# IPSv3_0.net
KiCad netlist of a schematic drawn in EAGLE
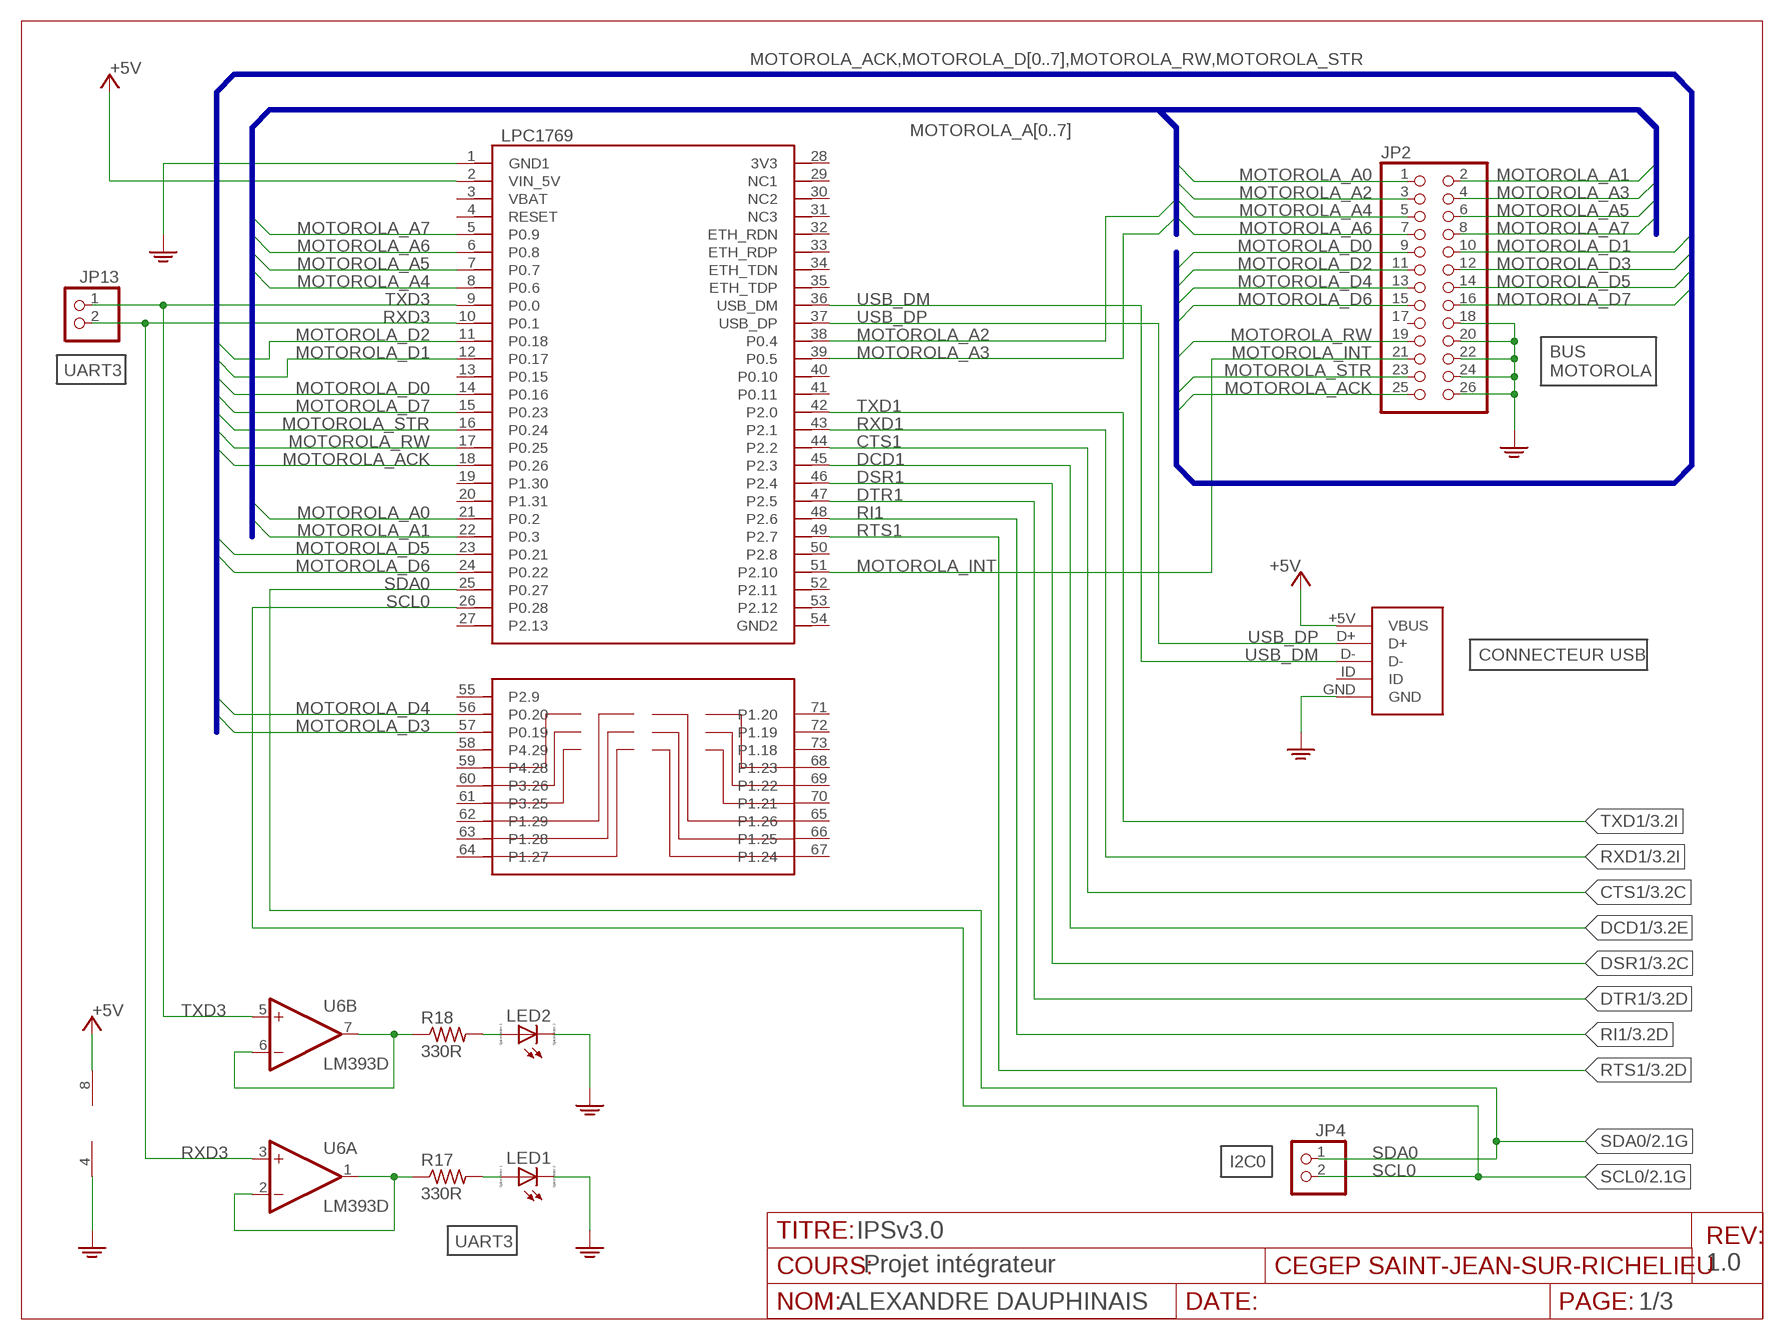
[diagram p0: schematic, sheet 1]
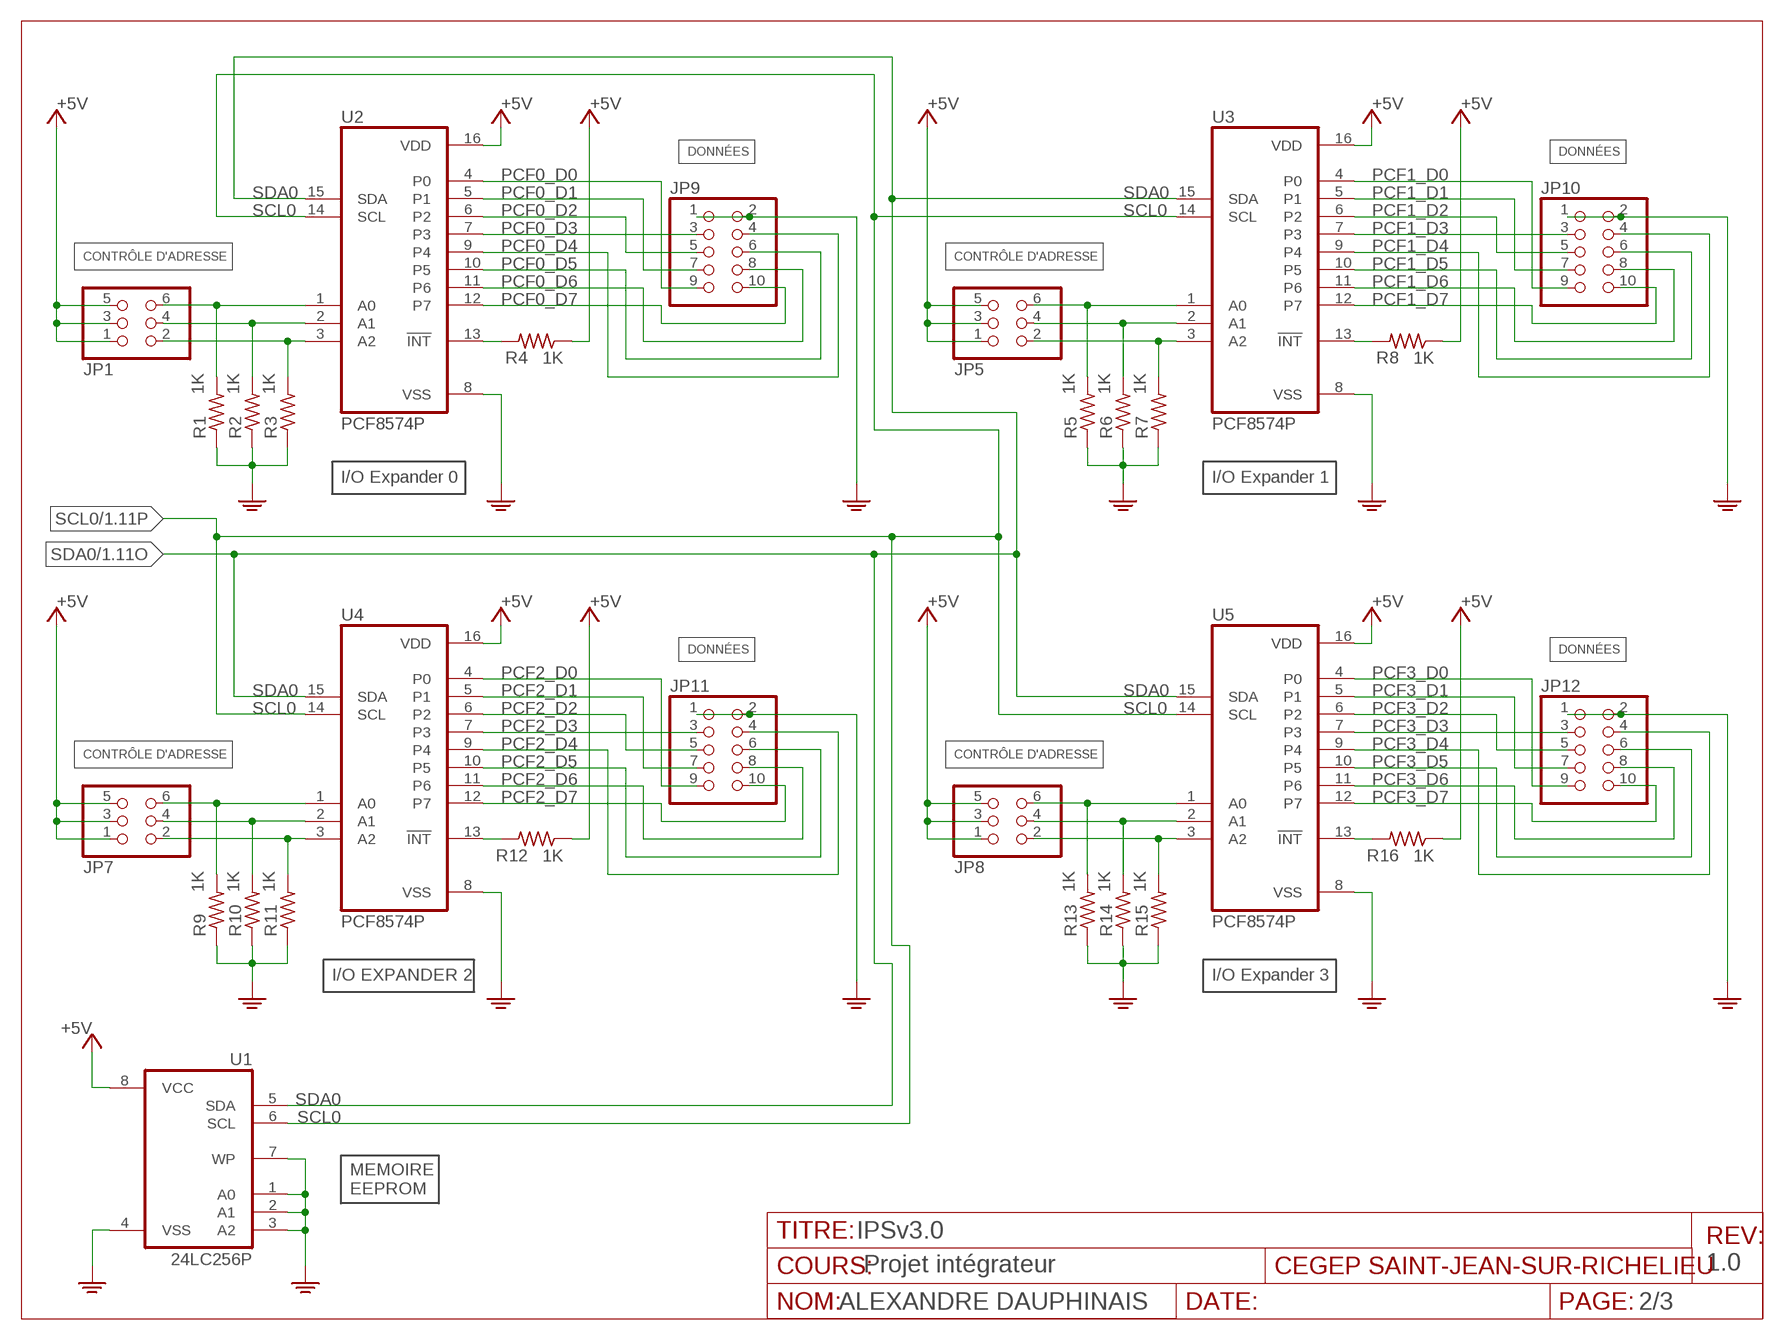
[diagram p1: schematic, sheet 2]
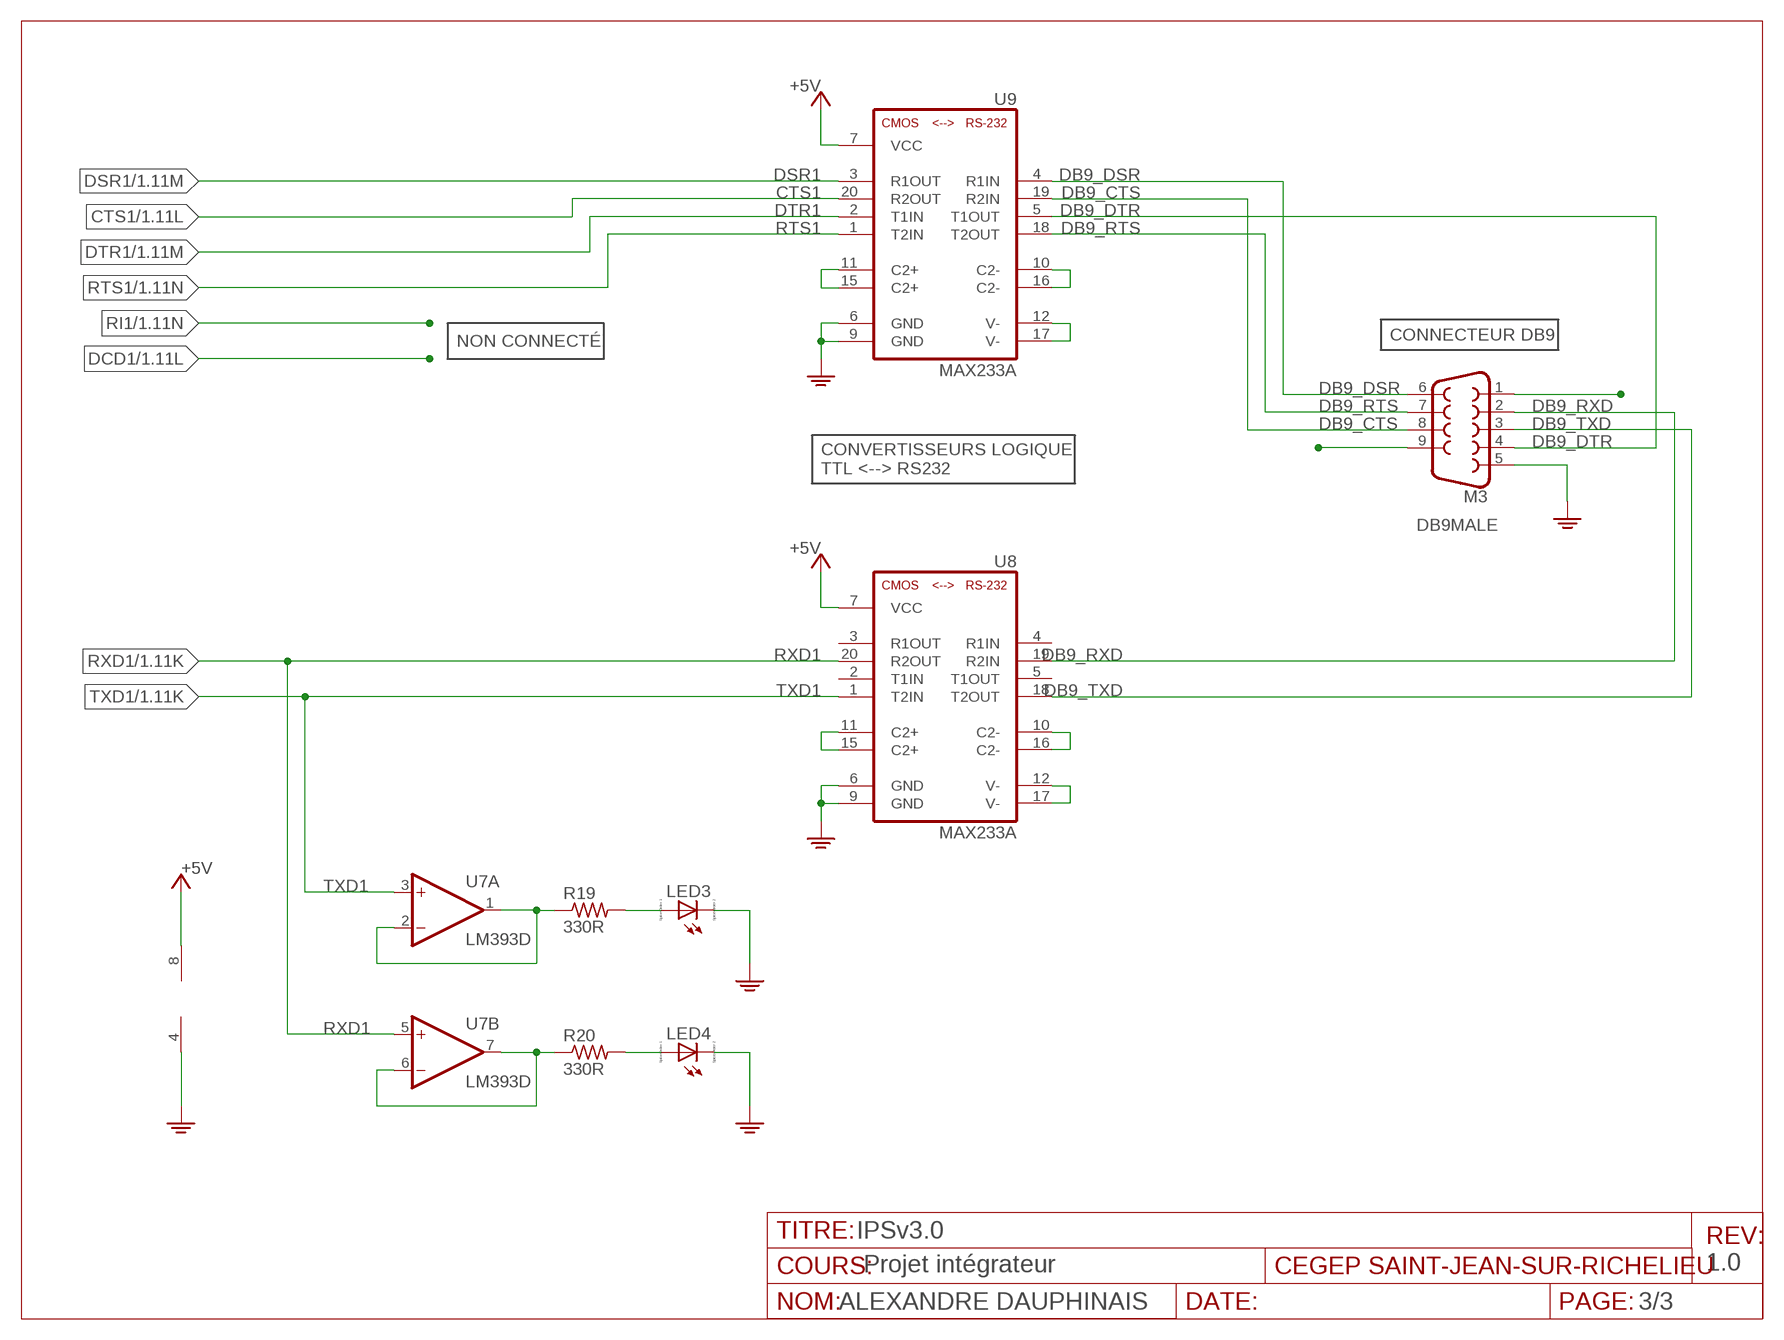
[diagram p2: schematic, sheet 3]

(export (version "E")
  (design (tool "Eeschema 10.0.6"))
  (components
    (comp (ref "JP2")
      (value "PINHD-02X13M")
      (footprint "eagle-import:02X13M")
      (libsource (lib "eagle-import") (part "PINHD-02X13M"))
    )
    (comp (ref "JP4")
      (value "PINHD-01X02M")
      (footprint "eagle-import:01X02M")
      (libsource (lib "eagle-import") (part "PINHD-01X02M"))
    )
    (comp (ref "JP13")
      (value "PINHD-01X02M")
      (footprint "eagle-import:01X02M")
      (libsource (lib "eagle-import") (part "PINHD-01X02M"))
    )
    (comp (ref "LED1")
      (value "LED_BLEU")
      (footprint "eagle-import:LED_1206")
      (libsource (lib "eagle-import") (part "LED_E"))
    )
    (comp (ref "LED2")
      (value "LED_JAUNE")
      (footprint "eagle-import:LED_1206")
      (libsource (lib "eagle-import") (part "LED_E"))
    )
    (comp (ref "M1")
      (value "LPC_LPC1769")
      (footprint "eagle-import:LPC_LPC1769")
      (libsource (lib "eagle-import") (part "LPC_LPC1769"))
    )
    (comp (ref "M2")
      (value "USB-MICRO-BREAKOUT")
      (footprint "eagle-import:USB-MICRO-BREAKOUT")
      (libsource (lib "eagle-import") (part "USB-MICRO-BREAKOUT"))
    )
    (comp (ref "R17")
      (value "330R")
      (footprint "eagle-import:R1206")
      (libsource (lib "eagle-import") (part "R-US_R1206"))
    )
    (comp (ref "R18")
      (value "330R")
      (footprint "eagle-import:R1206")
      (libsource (lib "eagle-import") (part "R-US_R1206"))
    )
    (comp (ref "U6")
      (value "LM393D")
      (footprint "eagle-import:SO08")
      (libsource (lib "eagle-import") (part "LM393D"))
    )
    (comp (ref "JP1")
      (value "PINHD-02X03M")
      (footprint "eagle-import:02X03M")
      (libsource (lib "eagle-import") (part "PINHD-02X03M"))
    )
    (comp (ref "JP5")
      (value "PINHD-02X03M")
      (footprint "eagle-import:02X03M")
      (libsource (lib "eagle-import") (part "PINHD-02X03M"))
    )
    (comp (ref "JP7")
      (value "PINHD-02X03M")
      (footprint "eagle-import:02X03M")
      (libsource (lib "eagle-import") (part "PINHD-02X03M"))
    )
    (comp (ref "JP8")
      (value "PINHD-02X03M")
      (footprint "eagle-import:02X03M")
      (libsource (lib "eagle-import") (part "PINHD-02X03M"))
    )
    (comp (ref "JP9")
      (value "PINHD-02X05M")
      (footprint "eagle-import:02X05M")
      (libsource (lib "eagle-import") (part "PINHD-02X05M"))
    )
    (comp (ref "JP10")
      (value "PINHD-02X05M")
      (footprint "eagle-import:02X05M")
      (libsource (lib "eagle-import") (part "PINHD-02X05M"))
    )
    (comp (ref "JP11")
      (value "PINHD-02X05M")
      (footprint "eagle-import:02X05M")
      (libsource (lib "eagle-import") (part "PINHD-02X05M"))
    )
    (comp (ref "JP12")
      (value "PINHD-02X05M")
      (footprint "eagle-import:02X05M")
      (libsource (lib "eagle-import") (part "PINHD-02X05M"))
    )
    (comp (ref "R1")
      (value "1K")
      (footprint "eagle-import:R1206")
      (libsource (lib "eagle-import") (part "R-US_R1206"))
    )
    (comp (ref "R2")
      (value "1K")
      (footprint "eagle-import:R1206")
      (libsource (lib "eagle-import") (part "R-US_R1206"))
    )
    (comp (ref "R3")
      (value "1K")
      (footprint "eagle-import:R1206")
      (libsource (lib "eagle-import") (part "R-US_R1206"))
    )
    (comp (ref "R4")
      (value "1K")
      (footprint "eagle-import:R1206")
      (libsource (lib "eagle-import") (part "R-US_R1206"))
    )
    (comp (ref "R5")
      (value "1K")
      (footprint "eagle-import:R1206")
      (libsource (lib "eagle-import") (part "R-US_R1206"))
    )
    (comp (ref "R6")
      (value "1K")
      (footprint "eagle-import:R1206")
      (libsource (lib "eagle-import") (part "R-US_R1206"))
    )
    (comp (ref "R7")
      (value "1K")
      (footprint "eagle-import:R1206")
      (libsource (lib "eagle-import") (part "R-US_R1206"))
    )
    (comp (ref "R8")
      (value "1K")
      (footprint "eagle-import:R1206")
      (libsource (lib "eagle-import") (part "R-US_R1206"))
    )
    (comp (ref "R9")
      (value "1K")
      (footprint "eagle-import:R1206")
      (libsource (lib "eagle-import") (part "R-US_R1206"))
    )
    (comp (ref "R10")
      (value "1K")
      (footprint "eagle-import:R1206")
      (libsource (lib "eagle-import") (part "R-US_R1206"))
    )
    (comp (ref "R11")
      (value "1K")
      (footprint "eagle-import:R1206")
      (libsource (lib "eagle-import") (part "R-US_R1206"))
    )
    (comp (ref "R12")
      (value "1K")
      (footprint "eagle-import:R1206")
      (libsource (lib "eagle-import") (part "R-US_R1206"))
    )
    (comp (ref "R13")
      (value "1K")
      (footprint "eagle-import:R1206")
      (libsource (lib "eagle-import") (part "R-US_R1206"))
    )
    (comp (ref "R14")
      (value "1K")
      (footprint "eagle-import:R1206")
      (libsource (lib "eagle-import") (part "R-US_R1206"))
    )
    (comp (ref "R15")
      (value "1K")
      (footprint "eagle-import:R1206")
      (libsource (lib "eagle-import") (part "R-US_R1206"))
    )
    (comp (ref "R16")
      (value "1K")
      (footprint "eagle-import:R1206")
      (libsource (lib "eagle-import") (part "R-US_R1206"))
    )
    (comp (ref "U1")
      (value "24LC256P")
      (footprint "eagle-import:DIL08")
      (libsource (lib "eagle-import") (part "24LC256P"))
    )
    (comp (ref "U2")
      (value "PCF8574P")
      (footprint "eagle-import:DIL16")
      (libsource (lib "eagle-import") (part "PCF8574P"))
    )
    (comp (ref "U3")
      (value "PCF8574P")
      (footprint "eagle-import:DIL16")
      (libsource (lib "eagle-import") (part "PCF8574P"))
    )
    (comp (ref "U4")
      (value "PCF8574P")
      (footprint "eagle-import:DIL16")
      (libsource (lib "eagle-import") (part "PCF8574P"))
    )
    (comp (ref "U5")
      (value "PCF8574P")
      (footprint "eagle-import:DIL16")
      (libsource (lib "eagle-import") (part "PCF8574P"))
    )
    (comp (ref "LED3")
      (value "LED_JAUNE")
      (footprint "eagle-import:LED_1206")
      (libsource (lib "eagle-import") (part "LED_E"))
    )
    (comp (ref "LED4")
      (value "LED_BLEU")
      (footprint "eagle-import:LED_1206")
      (libsource (lib "eagle-import") (part "LED_E"))
    )
    (comp (ref "M3")
      (value "DB9MALE")
      (footprint "eagle-import:DB9")
      (libsource (lib "eagle-import") (part "DB9FEMALE"))
    )
    (comp (ref "R19")
      (value "330R")
      (footprint "eagle-import:R1206")
      (libsource (lib "eagle-import") (part "R-US_R1206"))
    )
    (comp (ref "R20")
      (value "330R")
      (footprint "eagle-import:R1206")
      (libsource (lib "eagle-import") (part "R-US_R1206"))
    )
    (comp (ref "U7")
      (value "LM393D")
      (footprint "eagle-import:SO08")
      (libsource (lib "eagle-import") (part "LM393D"))
    )
    (comp (ref "U8")
      (value "MAX233A")
      (footprint "eagle-import:DIL20")
      (libsource (lib "eagle-import") (part "MAX233ACPP"))
    )
    (comp (ref "U9")
      (value "MAX233A")
      (footprint "eagle-import:DIL20")
      (libsource (lib "eagle-import") (part "MAX233ACPP"))
    )
  )
  (nets
    (net (code "1") (name "+5V") (class "Default")
      (node (ref "JP1") (pin "1") (pinfunction "1_1") (pintype "passive"))
      (node (ref "JP1") (pin "3") (pinfunction "3_3") (pintype "passive"))
      (node (ref "JP1") (pin "5") (pinfunction "5_5") (pintype "passive"))
      (node (ref "JP5") (pin "1") (pinfunction "1_1") (pintype "passive"))
      (node (ref "JP5") (pin "3") (pinfunction "3_3") (pintype "passive"))
      (node (ref "JP5") (pin "5") (pinfunction "5_5") (pintype "passive"))
      (node (ref "JP7") (pin "1") (pinfunction "1_1") (pintype "passive"))
      (node (ref "JP7") (pin "3") (pinfunction "3_3") (pintype "passive"))
      (node (ref "JP7") (pin "5") (pinfunction "5_5") (pintype "passive"))
      (node (ref "JP8") (pin "1") (pinfunction "1_1") (pintype "passive"))
      (node (ref "JP8") (pin "3") (pinfunction "3_3") (pintype "passive"))
      (node (ref "JP8") (pin "5") (pinfunction "5_5") (pintype "passive"))
      (node (ref "M1") (pin "2") (pinfunction "VIN_5V_2") (pintype "bidirectional"))
      (node (ref "M2") (pin "+5V") (pinfunction "VBUS_+5V") (pintype "power_in"))
      (node (ref "R12") (pin "1") (pinfunction "1_1") (pintype "passive"))
      (node (ref "R16") (pin "1") (pinfunction "1_1") (pintype "passive"))
      (node (ref "R4") (pin "1") (pinfunction "1_1") (pintype "passive"))
      (node (ref "R8") (pin "1") (pinfunction "1_1") (pintype "passive"))
      (node (ref "U1") (pin "8") (pinfunction "VCC_8") (pintype "power_in"))
      (node (ref "U2") (pin "16") (pinfunction "VDD_16") (pintype "power_in"))
      (node (ref "U3") (pin "16") (pinfunction "VDD_16") (pintype "power_in"))
      (node (ref "U4") (pin "16") (pinfunction "VDD_16") (pintype "power_in"))
      (node (ref "U5") (pin "16") (pinfunction "VDD_16") (pintype "power_in"))
      (node (ref "U6") (pin "8") (pinfunction "V+_8") (pintype "power_in"))
      (node (ref "U7") (pin "8") (pinfunction "V+_8") (pintype "power_in"))
      (node (ref "U8") (pin "7") (pinfunction "VCC_7") (pintype "power_in"))
      (node (ref "U9") (pin "7") (pinfunction "VCC_7") (pintype "power_in"))
    )
    (net (code "4") (name "CTS1") (class "Default")
      (node (ref "M1") (pin "44") (pinfunction "P2.2_44") (pintype "bidirectional"))
      (node (ref "U9") (pin "20") (pinfunction "R2OUT_20") (pintype "output"))
    )
    (net (code "5") (name "DB9_CTS") (class "Default")
      (node (ref "M3") (pin "8") (pinfunction "8_8") (pintype "passive"))
      (node (ref "U9") (pin "19") (pinfunction "R2IN_19") (pintype "input"))
    )
    (net (code "6") (name "DB9_DSR") (class "Default")
      (node (ref "M3") (pin "6") (pinfunction "6_6") (pintype "passive"))
      (node (ref "U9") (pin "4") (pinfunction "R1IN_4") (pintype "input"))
    )
    (net (code "7") (name "DB9_DTR") (class "Default")
      (node (ref "M3") (pin "4") (pinfunction "4_4") (pintype "passive"))
      (node (ref "U9") (pin "5") (pinfunction "T1OUT_5") (pintype "output"))
    )
    (net (code "8") (name "DB9_RTS") (class "Default")
      (node (ref "M3") (pin "7") (pinfunction "7_7") (pintype "passive"))
      (node (ref "U9") (pin "18") (pinfunction "T2OUT_18") (pintype "output"))
    )
    (net (code "9") (name "DB9_RXD") (class "Default")
      (node (ref "M3") (pin "2") (pinfunction "2_2") (pintype "passive"))
      (node (ref "U8") (pin "19") (pinfunction "R2IN_19") (pintype "input"))
    )
    (net (code "10") (name "DB9_TXD") (class "Default")
      (node (ref "M3") (pin "3") (pinfunction "3_3") (pintype "passive"))
      (node (ref "U8") (pin "18") (pinfunction "T2OUT_18") (pintype "output"))
    )
    (net (code "11") (name "DCD1") (class "Default")
      (node (ref "M1") (pin "45") (pinfunction "P2.3_45") (pintype "bidirectional"))
    )
    (net (code "12") (name "DSR1") (class "Default")
      (node (ref "M1") (pin "46") (pinfunction "P2.4_46") (pintype "bidirectional"))
      (node (ref "U9") (pin "3") (pinfunction "R1OUT_3") (pintype "output"))
    )
    (net (code "13") (name "DTR1") (class "Default")
      (node (ref "M1") (pin "47") (pinfunction "P2.5_47") (pintype "bidirectional"))
      (node (ref "U9") (pin "2") (pinfunction "T1IN_2") (pintype "input"))
    )
    (net (code "14") (name "GND") (class "Default")
      (node (ref "JP10") (pin "1") (pinfunction "1_1") (pintype "passive"))
      (node (ref "JP10") (pin "2") (pinfunction "2_2") (pintype "passive"))
      (node (ref "JP11") (pin "1") (pinfunction "1_1") (pintype "passive"))
      (node (ref "JP11") (pin "2") (pinfunction "2_2") (pintype "passive"))
      (node (ref "JP12") (pin "1") (pinfunction "1_1") (pintype "passive"))
      (node (ref "JP12") (pin "2") (pinfunction "2_2") (pintype "passive"))
      (node (ref "JP2") (pin "18") (pinfunction "18_18") (pintype "passive"))
      (node (ref "JP2") (pin "20") (pinfunction "20_20") (pintype "passive"))
      (node (ref "JP2") (pin "22") (pinfunction "22_22") (pintype "passive"))
      (node (ref "JP2") (pin "24") (pinfunction "24_24") (pintype "passive"))
      (node (ref "JP2") (pin "26") (pinfunction "26_26") (pintype "passive"))
      (node (ref "JP9") (pin "1") (pinfunction "1_1") (pintype "passive"))
      (node (ref "JP9") (pin "2") (pinfunction "2_2") (pintype "passive"))
      (node (ref "LED1") (pin "C") (pinfunction "C_C") (pintype "passive"))
      (node (ref "LED2") (pin "C") (pinfunction "C_C") (pintype "passive"))
      (node (ref "LED3") (pin "C") (pinfunction "C_C") (pintype "passive"))
      (node (ref "LED4") (pin "C") (pinfunction "C_C") (pintype "passive"))
      (node (ref "M1") (pin "1") (pinfunction "GND1_1") (pintype "bidirectional"))
      (node (ref "M2") (pin "GND") (pinfunction "GND_GND") (pintype "power_in"))
      (node (ref "M3") (pin "5") (pinfunction "5_5") (pintype "passive"))
      (node (ref "R1") (pin "1") (pinfunction "1_1") (pintype "passive"))
      (node (ref "R10") (pin "1") (pinfunction "1_1") (pintype "passive"))
      (node (ref "R11") (pin "1") (pinfunction "1_1") (pintype "passive"))
      (node (ref "R13") (pin "1") (pinfunction "1_1") (pintype "passive"))
      (node (ref "R14") (pin "1") (pinfunction "1_1") (pintype "passive"))
      (node (ref "R15") (pin "1") (pinfunction "1_1") (pintype "passive"))
      (node (ref "R2") (pin "1") (pinfunction "1_1") (pintype "passive"))
      (node (ref "R3") (pin "1") (pinfunction "1_1") (pintype "passive"))
      (node (ref "R5") (pin "1") (pinfunction "1_1") (pintype "passive"))
      (node (ref "R6") (pin "1") (pinfunction "1_1") (pintype "passive"))
      (node (ref "R7") (pin "1") (pinfunction "1_1") (pintype "passive"))
      (node (ref "R9") (pin "1") (pinfunction "1_1") (pintype "passive"))
      (node (ref "U1") (pin "1") (pinfunction "A0_1") (pintype "input"))
      (node (ref "U1") (pin "2") (pinfunction "A1_2") (pintype "input"))
      (node (ref "U1") (pin "3") (pinfunction "A2_3") (pintype "input"))
      (node (ref "U1") (pin "4") (pinfunction "VSS_4") (pintype "power_in"))
      (node (ref "U1") (pin "7") (pinfunction "WP_7") (pintype "input"))
      (node (ref "U2") (pin "8") (pinfunction "VSS_8") (pintype "power_in"))
      (node (ref "U3") (pin "8") (pinfunction "VSS_8") (pintype "power_in"))
      (node (ref "U4") (pin "8") (pinfunction "VSS_8") (pintype "power_in"))
      (node (ref "U5") (pin "8") (pinfunction "VSS_8") (pintype "power_in"))
      (node (ref "U6") (pin "4") (pinfunction "V-_4") (pintype "power_in"))
      (node (ref "U7") (pin "4") (pinfunction "V-_4") (pintype "power_in"))
      (node (ref "U8") (pin "6") (pinfunction "GND_6") (pintype "power_in"))
      (node (ref "U8") (pin "9") (pinfunction "GND_9") (pintype "power_in"))
      (node (ref "U9") (pin "6") (pinfunction "GND_6") (pintype "power_in"))
      (node (ref "U9") (pin "9") (pinfunction "GND_9") (pintype "power_in"))
    )
    (net (code "15") (name "MOTOROLA_A0") (class "Default")
      (node (ref "JP2") (pin "1") (pinfunction "1_1") (pintype "passive"))
      (node (ref "M1") (pin "21") (pinfunction "P0.2_21") (pintype "bidirectional"))
    )
    (net (code "16") (name "MOTOROLA_A1") (class "Default")
      (node (ref "JP2") (pin "2") (pinfunction "2_2") (pintype "passive"))
      (node (ref "M1") (pin "22") (pinfunction "P0.3_22") (pintype "bidirectional"))
    )
    (net (code "17") (name "MOTOROLA_A2") (class "Default")
      (node (ref "JP2") (pin "3") (pinfunction "3_3") (pintype "passive"))
      (node (ref "M1") (pin "38") (pinfunction "P0.4_38") (pintype "bidirectional"))
    )
    (net (code "18") (name "MOTOROLA_A3") (class "Default")
      (node (ref "JP2") (pin "4") (pinfunction "4_4") (pintype "passive"))
      (node (ref "M1") (pin "39") (pinfunction "P0.5_39") (pintype "bidirectional"))
    )
    (net (code "19") (name "MOTOROLA_A4") (class "Default")
      (node (ref "JP2") (pin "5") (pinfunction "5_5") (pintype "passive"))
      (node (ref "M1") (pin "8") (pinfunction "P0.6_8") (pintype "bidirectional"))
    )
    (net (code "20") (name "MOTOROLA_A5") (class "Default")
      (node (ref "JP2") (pin "6") (pinfunction "6_6") (pintype "passive"))
      (node (ref "M1") (pin "7") (pinfunction "P0.7_7") (pintype "bidirectional"))
    )
    (net (code "21") (name "MOTOROLA_A6") (class "Default")
      (node (ref "JP2") (pin "7") (pinfunction "7_7") (pintype "passive"))
      (node (ref "M1") (pin "6") (pinfunction "P0.8_6") (pintype "bidirectional"))
    )
    (net (code "22") (name "MOTOROLA_A7") (class "Default")
      (node (ref "JP2") (pin "8") (pinfunction "8_8") (pintype "passive"))
      (node (ref "M1") (pin "5") (pinfunction "P0.9_5") (pintype "bidirectional"))
    )
    (net (code "23") (name "MOTOROLA_ACK") (class "Default")
      (node (ref "JP2") (pin "25") (pinfunction "25_25") (pintype "passive"))
      (node (ref "M1") (pin "18") (pinfunction "P0.26_18") (pintype "bidirectional"))
    )
    (net (code "24") (name "MOTOROLA_D0") (class "Default")
      (node (ref "JP2") (pin "9") (pinfunction "9_9") (pintype "passive"))
      (node (ref "M1") (pin "14") (pinfunction "P0.16_14") (pintype "bidirectional"))
    )
    (net (code "25") (name "MOTOROLA_D1") (class "Default")
      (node (ref "JP2") (pin "10") (pinfunction "10_10") (pintype "passive"))
      (node (ref "M1") (pin "12") (pinfunction "P0.17_12") (pintype "bidirectional"))
    )
    (net (code "26") (name "MOTOROLA_D2") (class "Default")
      (node (ref "JP2") (pin "11") (pinfunction "11_11") (pintype "passive"))
      (node (ref "M1") (pin "11") (pinfunction "P0.18_11") (pintype "bidirectional"))
    )
    (net (code "27") (name "MOTOROLA_D3") (class "Default")
      (node (ref "JP2") (pin "12") (pinfunction "12_12") (pintype "passive"))
      (node (ref "M1") (pin "57") (pinfunction "P0.19_57") (pintype "bidirectional"))
    )
    (net (code "28") (name "MOTOROLA_D4") (class "Default")
      (node (ref "JP2") (pin "13") (pinfunction "13_13") (pintype "passive"))
      (node (ref "M1") (pin "56") (pinfunction "P0.20_56") (pintype "bidirectional"))
    )
    (net (code "29") (name "MOTOROLA_D5") (class "Default")
      (node (ref "JP2") (pin "14") (pinfunction "14_14") (pintype "passive"))
      (node (ref "M1") (pin "23") (pinfunction "P0.21_23") (pintype "bidirectional"))
    )
    (net (code "30") (name "MOTOROLA_D6") (class "Default")
      (node (ref "JP2") (pin "15") (pinfunction "15_15") (pintype "passive"))
      (node (ref "M1") (pin "24") (pinfunction "P0.22_24") (pintype "bidirectional"))
    )
    (net (code "31") (name "MOTOROLA_D7") (class "Default")
      (node (ref "JP2") (pin "16") (pinfunction "16_16") (pintype "passive"))
      (node (ref "M1") (pin "15") (pinfunction "P0.23_15") (pintype "bidirectional"))
    )
    (net (code "32") (name "MOTOROLA_INT") (class "Default")
      (node (ref "JP2") (pin "21") (pinfunction "21_21") (pintype "passive"))
      (node (ref "M1") (pin "51") (pinfunction "P2.10_51") (pintype "bidirectional"))
    )
    (net (code "33") (name "MOTOROLA_RW") (class "Default")
      (node (ref "JP2") (pin "19") (pinfunction "19_19") (pintype "passive"))
      (node (ref "M1") (pin "17") (pinfunction "P0.25_17") (pintype "bidirectional"))
    )
    (net (code "34") (name "MOTOROLA_STR") (class "Default")
      (node (ref "JP2") (pin "23") (pinfunction "23_23") (pintype "passive"))
      (node (ref "M1") (pin "16") (pinfunction "P0.24_16") (pintype "bidirectional"))
    )
    (net (code "35") (name "Net-(LED1-PadA)") (class "Default")
      (node (ref "LED1") (pin "A") (pinfunction "A_A") (pintype "passive"))
      (node (ref "R17") (pin "2") (pinfunction "2_2") (pintype "passive"))
    )
    (net (code "36") (name "Net-(LED2-PadA)") (class "Default")
      (node (ref "LED2") (pin "A") (pinfunction "A_A") (pintype "passive"))
      (node (ref "R18") (pin "2") (pinfunction "2_2") (pintype "passive"))
    )
    (net (code "37") (name "Net-(LED3-PadA)") (class "Default")
      (node (ref "LED3") (pin "A") (pinfunction "A_A") (pintype "passive"))
      (node (ref "R19") (pin "2") (pinfunction "2_2") (pintype "passive"))
    )
    (net (code "38") (name "Net-(LED4-PadA)") (class "Default")
      (node (ref "LED4") (pin "A") (pinfunction "A_A") (pintype "passive"))
      (node (ref "R20") (pin "2") (pinfunction "2_2") (pintype "passive"))
    )
    (net (code "39") (name "Net-(U2-A0)") (class "Default")
      (node (ref "JP1") (pin "6") (pinfunction "6_6") (pintype "passive"))
      (node (ref "R1") (pin "2") (pinfunction "2_2") (pintype "passive"))
      (node (ref "U2") (pin "1") (pinfunction "A0_1") (pintype "input"))
    )
    (net (code "40") (name "Net-(U2-A1)") (class "Default")
      (node (ref "JP1") (pin "4") (pinfunction "4_4") (pintype "passive"))
      (node (ref "R2") (pin "2") (pinfunction "2_2") (pintype "passive"))
      (node (ref "U2") (pin "2") (pinfunction "A1_2") (pintype "input"))
    )
    (net (code "41") (name "Net-(U2-A2)") (class "Default")
      (node (ref "JP1") (pin "2") (pinfunction "2_2") (pintype "passive"))
      (node (ref "R3") (pin "2") (pinfunction "2_2") (pintype "passive"))
      (node (ref "U2") (pin "3") (pinfunction "A2_3") (pintype "input"))
    )
    (net (code "42") (name "Net-(U2-~{INT})") (class "Default")
      (node (ref "R4") (pin "2") (pinfunction "2_2") (pintype "passive"))
      (node (ref "U2") (pin "13") (pinfunction "~{INT}_13") (pintype "output"))
    )
    (net (code "43") (name "Net-(U3-A0)") (class "Default")
      (node (ref "JP5") (pin "6") (pinfunction "6_6") (pintype "passive"))
      (node (ref "R5") (pin "2") (pinfunction "2_2") (pintype "passive"))
      (node (ref "U3") (pin "1") (pinfunction "A0_1") (pintype "input"))
    )
    (net (code "44") (name "Net-(U3-A1)") (class "Default")
      (node (ref "JP5") (pin "4") (pinfunction "4_4") (pintype "passive"))
      (node (ref "R6") (pin "2") (pinfunction "2_2") (pintype "passive"))
      (node (ref "U3") (pin "2") (pinfunction "A1_2") (pintype "input"))
    )
    (net (code "45") (name "Net-(U3-A2)") (class "Default")
      (node (ref "JP5") (pin "2") (pinfunction "2_2") (pintype "passive"))
      (node (ref "R7") (pin "2") (pinfunction "2_2") (pintype "passive"))
      (node (ref "U3") (pin "3") (pinfunction "A2_3") (pintype "input"))
    )
    (net (code "46") (name "Net-(U3-~{INT})") (class "Default")
      (node (ref "R8") (pin "2") (pinfunction "2_2") (pintype "passive"))
      (node (ref "U3") (pin "13") (pinfunction "~{INT}_13") (pintype "output"))
    )
    (net (code "47") (name "Net-(U4-A0)") (class "Default")
      (node (ref "JP7") (pin "6") (pinfunction "6_6") (pintype "passive"))
      (node (ref "R9") (pin "2") (pinfunction "2_2") (pintype "passive"))
      (node (ref "U4") (pin "1") (pinfunction "A0_1") (pintype "input"))
    )
    (net (code "48") (name "Net-(U4-A1)") (class "Default")
      (node (ref "JP7") (pin "4") (pinfunction "4_4") (pintype "passive"))
      (node (ref "R10") (pin "2") (pinfunction "2_2") (pintype "passive"))
      (node (ref "U4") (pin "2") (pinfunction "A1_2") (pintype "input"))
    )
    (net (code "49") (name "Net-(U4-A2)") (class "Default")
      (node (ref "JP7") (pin "2") (pinfunction "2_2") (pintype "passive"))
      (node (ref "R11") (pin "2") (pinfunction "2_2") (pintype "passive"))
      (node (ref "U4") (pin "3") (pinfunction "A2_3") (pintype "input"))
    )
    (net (code "50") (name "Net-(U4-~{INT})") (class "Default")
      (node (ref "R12") (pin "2") (pinfunction "2_2") (pintype "passive"))
      (node (ref "U4") (pin "13") (pinfunction "~{INT}_13") (pintype "output"))
    )
    (net (code "51") (name "Net-(U5-A0)") (class "Default")
      (node (ref "JP8") (pin "6") (pinfunction "6_6") (pintype "passive"))
      (node (ref "R13") (pin "2") (pinfunction "2_2") (pintype "passive"))
      (node (ref "U5") (pin "1") (pinfunction "A0_1") (pintype "input"))
    )
    (net (code "52") (name "Net-(U5-A1)") (class "Default")
      (node (ref "JP8") (pin "4") (pinfunction "4_4") (pintype "passive"))
      (node (ref "R14") (pin "2") (pinfunction "2_2") (pintype "passive"))
      (node (ref "U5") (pin "2") (pinfunction "A1_2") (pintype "input"))
    )
    (net (code "53") (name "Net-(U5-A2)") (class "Default")
      (node (ref "JP8") (pin "2") (pinfunction "2_2") (pintype "passive"))
      (node (ref "R15") (pin "2") (pinfunction "2_2") (pintype "passive"))
      (node (ref "U5") (pin "3") (pinfunction "A2_3") (pintype "input"))
    )
    (net (code "54") (name "Net-(U5-~{INT})") (class "Default")
      (node (ref "R16") (pin "2") (pinfunction "2_2") (pintype "passive"))
      (node (ref "U5") (pin "13") (pinfunction "~{INT}_13") (pintype "output"))
    )
    (net (code "55") (name "Net-(U6A--IN)") (class "Default")
      (node (ref "R17") (pin "1") (pinfunction "1_1") (pintype "passive"))
      (node (ref "U6") (pin "1") (pinfunction "OUT_1") (pintype "output"))
      (node (ref "U6") (pin "2") (pinfunction "-IN_2") (pintype "input"))
    )
    (net (code "56") (name "Net-(U6B--IN)") (class "Default")
      (node (ref "R18") (pin "1") (pinfunction "1_1") (pintype "passive"))
      (node (ref "U6") (pin "6") (pinfunction "-IN_6") (pintype "input"))
      (node (ref "U6") (pin "7") (pinfunction "OUT_7") (pintype "output"))
    )
    (net (code "57") (name "Net-(U7A--IN)") (class "Default")
      (node (ref "R19") (pin "1") (pinfunction "1_1") (pintype "passive"))
      (node (ref "U7") (pin "1") (pinfunction "OUT_1") (pintype "output"))
      (node (ref "U7") (pin "2") (pinfunction "-IN_2") (pintype "input"))
    )
    (net (code "58") (name "Net-(U7B--IN)") (class "Default")
      (node (ref "R20") (pin "1") (pinfunction "1_1") (pintype "passive"))
      (node (ref "U7") (pin "6") (pinfunction "-IN_6") (pintype "input"))
      (node (ref "U7") (pin "7") (pinfunction "OUT_7") (pintype "output"))
    )
    (net (code "59") (name "Net-(U8-C2+-Pad11)") (class "Default")
      (node (ref "U8") (pin "11") (pinfunction "C2+_11") (pintype "passive"))
      (node (ref "U8") (pin "15") (pinfunction "C2+_15") (pintype "passive"))
    )
    (net (code "60") (name "Net-(U8-C2--Pad10)") (class "Default")
      (node (ref "U8") (pin "10") (pinfunction "C2-_10") (pintype "passive"))
      (node (ref "U8") (pin "16") (pinfunction "C2-_16") (pintype "passive"))
    )
    (net (code "61") (name "Net-(U8-V--Pad12)") (class "Default")
      (node (ref "U8") (pin "12") (pinfunction "V-_12") (pintype "passive"))
      (node (ref "U8") (pin "17") (pinfunction "V-_17") (pintype "passive"))
    )
    (net (code "62") (name "Net-(U9-C2+-Pad11)") (class "Default")
      (node (ref "U9") (pin "11") (pinfunction "C2+_11") (pintype "passive"))
      (node (ref "U9") (pin "15") (pinfunction "C2+_15") (pintype "passive"))
    )
    (net (code "63") (name "Net-(U9-C2--Pad10)") (class "Default")
      (node (ref "U9") (pin "10") (pinfunction "C2-_10") (pintype "passive"))
      (node (ref "U9") (pin "16") (pinfunction "C2-_16") (pintype "passive"))
    )
    (net (code "64") (name "Net-(U9-V--Pad12)") (class "Default")
      (node (ref "U9") (pin "12") (pinfunction "V-_12") (pintype "passive"))
      (node (ref "U9") (pin "17") (pinfunction "V-_17") (pintype "passive"))
    )
    (net (code "65") (name "PCF0_D0") (class "Default")
      (node (ref "JP9") (pin "9") (pinfunction "9_9") (pintype "passive"))
      (node (ref "U2") (pin "4") (pinfunction "P0_4") (pintype "bidirectional"))
    )
    (net (code "66") (name "PCF0_D1") (class "Default")
      (node (ref "JP9") (pin "7") (pinfunction "7_7") (pintype "passive"))
      (node (ref "U2") (pin "5") (pinfunction "P1_5") (pintype "bidirectional"))
    )
    (net (code "67") (name "PCF0_D2") (class "Default")
      (node (ref "JP9") (pin "5") (pinfunction "5_5") (pintype "passive"))
      (node (ref "U2") (pin "6") (pinfunction "P2_6") (pintype "bidirectional"))
    )
    (net (code "68") (name "PCF0_D3") (class "Default")
      (node (ref "JP9") (pin "3") (pinfunction "3_3") (pintype "passive"))
      (node (ref "U2") (pin "7") (pinfunction "P3_7") (pintype "bidirectional"))
    )
    (net (code "69") (name "PCF0_D4") (class "Default")
      (node (ref "JP9") (pin "4") (pinfunction "4_4") (pintype "passive"))
      (node (ref "U2") (pin "9") (pinfunction "P4_9") (pintype "bidirectional"))
    )
    (net (code "70") (name "PCF0_D5") (class "Default")
      (node (ref "JP9") (pin "6") (pinfunction "6_6") (pintype "passive"))
      (node (ref "U2") (pin "10") (pinfunction "P5_10") (pintype "bidirectional"))
    )
    (net (code "71") (name "PCF0_D6") (class "Default")
      (node (ref "JP9") (pin "8") (pinfunction "8_8") (pintype "passive"))
      (node (ref "U2") (pin "11") (pinfunction "P6_11") (pintype "bidirectional"))
    )
    (net (code "72") (name "PCF0_D7") (class "Default")
      (node (ref "JP9") (pin "10") (pinfunction "10_10") (pintype "passive"))
      (node (ref "U2") (pin "12") (pinfunction "P7_12") (pintype "bidirectional"))
    )
    (net (code "73") (name "PCF1_D0") (class "Default")
      (node (ref "JP10") (pin "9") (pinfunction "9_9") (pintype "passive"))
      (node (ref "U3") (pin "4") (pinfunction "P0_4") (pintype "bidirectional"))
    )
    (net (code "74") (name "PCF1_D1") (class "Default")
      (node (ref "JP10") (pin "7") (pinfunction "7_7") (pintype "passive"))
      (node (ref "U3") (pin "5") (pinfunction "P1_5") (pintype "bidirectional"))
    )
    (net (code "75") (name "PCF1_D2") (class "Default")
      (node (ref "JP10") (pin "5") (pinfunction "5_5") (pintype "passive"))
      (node (ref "U3") (pin "6") (pinfunction "P2_6") (pintype "bidirectional"))
    )
    (net (code "76") (name "PCF1_D3") (class "Default")
      (node (ref "JP10") (pin "3") (pinfunction "3_3") (pintype "passive"))
      (node (ref "U3") (pin "7") (pinfunction "P3_7") (pintype "bidirectional"))
    )
    (net (code "77") (name "PCF1_D4") (class "Default")
      (node (ref "JP10") (pin "4") (pinfunction "4_4") (pintype "passive"))
      (node (ref "U3") (pin "9") (pinfunction "P4_9") (pintype "bidirectional"))
    )
    (net (code "78") (name "PCF1_D5") (class "Default")
      (node (ref "JP10") (pin "6") (pinfunction "6_6") (pintype "passive"))
      (node (ref "U3") (pin "10") (pinfunction "P5_10") (pintype "bidirectional"))
    )
    (net (code "79") (name "PCF1_D6") (class "Default")
      (node (ref "JP10") (pin "8") (pinfunction "8_8") (pintype "passive"))
      (node (ref "U3") (pin "11") (pinfunction "P6_11") (pintype "bidirectional"))
    )
    (net (code "80") (name "PCF1_D7") (class "Default")
      (node (ref "JP10") (pin "10") (pinfunction "10_10") (pintype "passive"))
      (node (ref "U3") (pin "12") (pinfunction "P7_12") (pintype "bidirectional"))
    )
    (net (code "81") (name "PCF2_D0") (class "Default")
      (node (ref "JP11") (pin "9") (pinfunction "9_9") (pintype "passive"))
      (node (ref "U4") (pin "4") (pinfunction "P0_4") (pintype "bidirectional"))
    )
    (net (code "82") (name "PCF2_D1") (class "Default")
      (node (ref "JP11") (pin "7") (pinfunction "7_7") (pintype "passive"))
      (node (ref "U4") (pin "5") (pinfunction "P1_5") (pintype "bidirectional"))
    )
    (net (code "83") (name "PCF2_D2") (class "Default")
      (node (ref "JP11") (pin "5") (pinfunction "5_5") (pintype "passive"))
      (node (ref "U4") (pin "6") (pinfunction "P2_6") (pintype "bidirectional"))
    )
    (net (code "84") (name "PCF2_D3") (class "Default")
      (node (ref "JP11") (pin "3") (pinfunction "3_3") (pintype "passive"))
      (node (ref "U4") (pin "7") (pinfunction "P3_7") (pintype "bidirectional"))
    )
    (net (code "85") (name "PCF2_D4") (class "Default")
      (node (ref "JP11") (pin "4") (pinfunction "4_4") (pintype "passive"))
      (node (ref "U4") (pin "9") (pinfunction "P4_9") (pintype "bidirectional"))
    )
    (net (code "86") (name "PCF2_D5") (class "Default")
      (node (ref "JP11") (pin "6") (pinfunction "6_6") (pintype "passive"))
      (node (ref "U4") (pin "10") (pinfunction "P5_10") (pintype "bidirectional"))
    )
    (net (code "87") (name "PCF2_D6") (class "Default")
      (node (ref "JP11") (pin "8") (pinfunction "8_8") (pintype "passive"))
      (node (ref "U4") (pin "11") (pinfunction "P6_11") (pintype "bidirectional"))
    )
    (net (code "88") (name "PCF2_D7") (class "Default")
      (node (ref "JP11") (pin "10") (pinfunction "10_10") (pintype "passive"))
      (node (ref "U4") (pin "12") (pinfunction "P7_12") (pintype "bidirectional"))
    )
    (net (code "89") (name "PCF3_D0") (class "Default")
      (node (ref "JP12") (pin "9") (pinfunction "9_9") (pintype "passive"))
      (node (ref "U5") (pin "4") (pinfunction "P0_4") (pintype "bidirectional"))
    )
    (net (code "90") (name "PCF3_D1") (class "Default")
      (node (ref "JP12") (pin "7") (pinfunction "7_7") (pintype "passive"))
      (node (ref "U5") (pin "5") (pinfunction "P1_5") (pintype "bidirectional"))
    )
    (net (code "91") (name "PCF3_D2") (class "Default")
      (node (ref "JP12") (pin "5") (pinfunction "5_5") (pintype "passive"))
      (node (ref "U5") (pin "6") (pinfunction "P2_6") (pintype "bidirectional"))
    )
    (net (code "92") (name "PCF3_D3") (class "Default")
      (node (ref "JP12") (pin "3") (pinfunction "3_3") (pintype "passive"))
      (node (ref "U5") (pin "7") (pinfunction "P3_7") (pintype "bidirectional"))
    )
    (net (code "93") (name "PCF3_D4") (class "Default")
      (node (ref "JP12") (pin "4") (pinfunction "4_4") (pintype "passive"))
      (node (ref "U5") (pin "9") (pinfunction "P4_9") (pintype "bidirectional"))
    )
    (net (code "94") (name "PCF3_D5") (class "Default")
      (node (ref "JP12") (pin "6") (pinfunction "6_6") (pintype "passive"))
      (node (ref "U5") (pin "10") (pinfunction "P5_10") (pintype "bidirectional"))
    )
    (net (code "95") (name "PCF3_D6") (class "Default")
      (node (ref "JP12") (pin "8") (pinfunction "8_8") (pintype "passive"))
      (node (ref "U5") (pin "11") (pinfunction "P6_11") (pintype "bidirectional"))
    )
    (net (code "96") (name "PCF3_D7") (class "Default")
      (node (ref "JP12") (pin "10") (pinfunction "10_10") (pintype "passive"))
      (node (ref "U5") (pin "12") (pinfunction "P7_12") (pintype "bidirectional"))
    )
    (net (code "97") (name "RI1") (class "Default")
      (node (ref "M1") (pin "48") (pinfunction "P2.6_48") (pintype "bidirectional"))
    )
    (net (code "98") (name "RTS1") (class "Default")
      (node (ref "M1") (pin "49") (pinfunction "P2.7_49") (pintype "bidirectional"))
      (node (ref "U9") (pin "1") (pinfunction "T2IN_1") (pintype "input"))
    )
    (net (code "99") (name "RXD1") (class "Default")
      (node (ref "M1") (pin "43") (pinfunction "P2.1_43") (pintype "bidirectional"))
      (node (ref "U7") (pin "5") (pinfunction "+IN_5") (pintype "input"))
      (node (ref "U8") (pin "20") (pinfunction "R2OUT_20") (pintype "output"))
    )
    (net (code "100") (name "RXD3") (class "Default")
      (node (ref "JP13") (pin "2") (pinfunction "2_2") (pintype "passive"))
      (node (ref "M1") (pin "10") (pinfunction "P0.1_10") (pintype "bidirectional"))
      (node (ref "U6") (pin "3") (pinfunction "+IN_3") (pintype "input"))
    )
    (net (code "101") (name "SCL0") (class "Default")
      (node (ref "JP4") (pin "2") (pinfunction "2_2") (pintype "passive"))
      (node (ref "M1") (pin "26") (pinfunction "P0.28_26") (pintype "bidirectional"))
      (node (ref "U1") (pin "6") (pinfunction "SCL_6") (pintype "input"))
      (node (ref "U2") (pin "14") (pinfunction "SCL_14") (pintype "input"))
      (node (ref "U3") (pin "14") (pinfunction "SCL_14") (pintype "input"))
      (node (ref "U4") (pin "14") (pinfunction "SCL_14") (pintype "input"))
      (node (ref "U5") (pin "14") (pinfunction "SCL_14") (pintype "input"))
    )
    (net (code "102") (name "SDA0") (class "Default")
      (node (ref "JP4") (pin "1") (pinfunction "1_1") (pintype "passive"))
      (node (ref "M1") (pin "25") (pinfunction "P0.27_25") (pintype "bidirectional"))
      (node (ref "U1") (pin "5") (pinfunction "SDA_5") (pintype "bidirectional"))
      (node (ref "U2") (pin "15") (pinfunction "SDA_15") (pintype "bidirectional"))
      (node (ref "U3") (pin "15") (pinfunction "SDA_15") (pintype "bidirectional"))
      (node (ref "U4") (pin "15") (pinfunction "SDA_15") (pintype "bidirectional"))
      (node (ref "U5") (pin "15") (pinfunction "SDA_15") (pintype "bidirectional"))
    )
    (net (code "103") (name "TXD1") (class "Default")
      (node (ref "M1") (pin "42") (pinfunction "P2.0_42") (pintype "bidirectional"))
      (node (ref "U7") (pin "3") (pinfunction "+IN_3") (pintype "input"))
      (node (ref "U8") (pin "1") (pinfunction "T2IN_1") (pintype "input"))
    )
    (net (code "104") (name "TXD3") (class "Default")
      (node (ref "JP13") (pin "1") (pinfunction "1_1") (pintype "passive"))
      (node (ref "M1") (pin "9") (pinfunction "P0.0_9") (pintype "bidirectional"))
      (node (ref "U6") (pin "5") (pinfunction "+IN_5") (pintype "input"))
    )
    (net (code "105") (name "USB_DM") (class "Default")
      (node (ref "M1") (pin "36") (pinfunction "USB_DM_36") (pintype "bidirectional"))
      (node (ref "M2") (pin "D-") (pinfunction "D-_D-") (pintype "bidirectional"))
    )
    (net (code "106") (name "USB_DP") (class "Default")
      (node (ref "M1") (pin "37") (pinfunction "USB_DP_37") (pintype "bidirectional"))
      (node (ref "M2") (pin "D+") (pinfunction "D+_D+") (pintype "bidirectional"))
    )
    (net (code "107") (name "unconnected-(JP2-Pad17)") (class "Default")
      (node (ref "JP2") (pin "17") (pinfunction "17_17") (pintype "passive"))
    )
    (net (code "108") (name "unconnected-(M1-3V3-Pad28)") (class "Default")
      (node (ref "M1") (pin "28") (pinfunction "3V3_28") (pintype "bidirectional"))
    )
    (net (code "109") (name "unconnected-(M1-ETH_RDN-Pad32)") (class "Default")
      (node (ref "M1") (pin "32") (pinfunction "ETH_RDN_32") (pintype "bidirectional"))
    )
    (net (code "110") (name "unconnected-(M1-ETH_RDP-Pad33)") (class "Default")
      (node (ref "M1") (pin "33") (pinfunction "ETH_RDP_33") (pintype "bidirectional"))
    )
    (net (code "111") (name "unconnected-(M1-ETH_TDN-Pad34)") (class "Default")
      (node (ref "M1") (pin "34") (pinfunction "ETH_TDN_34") (pintype "bidirectional"))
    )
    (net (code "112") (name "unconnected-(M1-ETH_TDP-Pad35)") (class "Default")
      (node (ref "M1") (pin "35") (pinfunction "ETH_TDP_35") (pintype "bidirectional"))
    )
    (net (code "113") (name "unconnected-(M1-GND2-Pad54)") (class "Default")
      (node (ref "M1") (pin "54") (pinfunction "GND2_54") (pintype "bidirectional"))
    )
    (net (code "114") (name "unconnected-(M1-NC1-Pad29)") (class "Default")
      (node (ref "M1") (pin "29") (pinfunction "NC1_29") (pintype "bidirectional"))
    )
    (net (code "115") (name "unconnected-(M1-NC2-Pad30)") (class "Default")
      (node (ref "M1") (pin "30") (pinfunction "NC2_30") (pintype "bidirectional"))
    )
    (net (code "116") (name "unconnected-(M1-NC3-Pad31)") (class "Default")
      (node (ref "M1") (pin "31") (pinfunction "NC3_31") (pintype "bidirectional"))
    )
    (net (code "117") (name "unconnected-(M1-P0.10-Pad40)") (class "Default")
      (node (ref "M1") (pin "40") (pinfunction "P0.10_40") (pintype "bidirectional"))
    )
    (net (code "118") (name "unconnected-(M1-P0.11-Pad41)") (class "Default")
      (node (ref "M1") (pin "41") (pinfunction "P0.11_41") (pintype "bidirectional"))
    )
    (net (code "119") (name "unconnected-(M1-P0.15-Pad13)") (class "Default")
      (node (ref "M1") (pin "13") (pinfunction "P0.15_13") (pintype "bidirectional"))
    )
    (net (code "120") (name "unconnected-(M1-P1.18-Pad73)") (class "Default")
      (node (ref "M1") (pin "73") (pinfunction "P1.18_73") (pintype "bidirectional"))
    )
    (net (code "121") (name "unconnected-(M1-P1.19-Pad72)") (class "Default")
      (node (ref "M1") (pin "72") (pinfunction "P1.19_72") (pintype "bidirectional"))
    )
    (net (code "122") (name "unconnected-(M1-P1.20-Pad71)") (class "Default")
      (node (ref "M1") (pin "71") (pinfunction "P1.20_71") (pintype "bidirectional"))
    )
    (net (code "123") (name "unconnected-(M1-P1.21-Pad70)") (class "Default")
      (node (ref "M1") (pin "70") (pinfunction "P1.21_70") (pintype "bidirectional"))
    )
    (net (code "124") (name "unconnected-(M1-P1.22-Pad69)") (class "Default")
      (node (ref "M1") (pin "69") (pinfunction "P1.22_69") (pintype "bidirectional"))
    )
    (net (code "125") (name "unconnected-(M1-P1.23-Pad68)") (class "Default")
      (node (ref "M1") (pin "68") (pinfunction "P1.23_68") (pintype "bidirectional"))
    )
    (net (code "126") (name "unconnected-(M1-P1.24-Pad67)") (class "Default")
      (node (ref "M1") (pin "67") (pinfunction "P1.24_67") (pintype "bidirectional"))
    )
    (net (code "127") (name "unconnected-(M1-P1.25-Pad66)") (class "Default")
      (node (ref "M1") (pin "66") (pinfunction "P1.25_66") (pintype "bidirectional"))
    )
    (net (code "128") (name "unconnected-(M1-P1.26-Pad65)") (class "Default")
      (node (ref "M1") (pin "65") (pinfunction "P1.26_65") (pintype "bidirectional"))
    )
    (net (code "129") (name "unconnected-(M1-P1.27-Pad64)") (class "Default")
      (node (ref "M1") (pin "64") (pinfunction "P1.27_64") (pintype "bidirectional"))
    )
    (net (code "130") (name "unconnected-(M1-P1.28-Pad63)") (class "Default")
      (node (ref "M1") (pin "63") (pinfunction "P1.28_63") (pintype "bidirectional"))
    )
    (net (code "131") (name "unconnected-(M1-P1.29-Pad62)") (class "Default")
      (node (ref "M1") (pin "62") (pinfunction "P1.29_62") (pintype "bidirectional"))
    )
    (net (code "132") (name "unconnected-(M1-P1.30-Pad19)") (class "Default")
      (node (ref "M1") (pin "19") (pinfunction "P1.30_19") (pintype "bidirectional"))
    )
    (net (code "133") (name "unconnected-(M1-P1.31-Pad20)") (class "Default")
      (node (ref "M1") (pin "20") (pinfunction "P1.31_20") (pintype "bidirectional"))
    )
    (net (code "134") (name "unconnected-(M1-P2.8-Pad50)") (class "Default")
      (node (ref "M1") (pin "50") (pinfunction "P2.8_50") (pintype "bidirectional"))
    )
    (net (code "135") (name "unconnected-(M1-P2.9-Pad55)") (class "Default")
      (node (ref "M1") (pin "55") (pinfunction "P2.9_55") (pintype "bidirectional"))
    )
    (net (code "136") (name "unconnected-(M1-P2.11-Pad52)") (class "Default")
      (node (ref "M1") (pin "52") (pinfunction "P2.11_52") (pintype "bidirectional"))
    )
    (net (code "137") (name "unconnected-(M1-P2.12-Pad53)") (class "Default")
      (node (ref "M1") (pin "53") (pinfunction "P2.12_53") (pintype "bidirectional"))
    )
    (net (code "138") (name "unconnected-(M1-P2.13-Pad27)") (class "Default")
      (node (ref "M1") (pin "27") (pinfunction "P2.13_27") (pintype "bidirectional"))
    )
    (net (code "139") (name "unconnected-(M1-P3.25-Pad61)") (class "Default")
      (node (ref "M1") (pin "61") (pinfunction "P3.25_61") (pintype "bidirectional"))
    )
    (net (code "140") (name "unconnected-(M1-P3.26-Pad60)") (class "Default")
      (node (ref "M1") (pin "60") (pinfunction "P3.26_60") (pintype "bidirectional"))
    )
    (net (code "141") (name "unconnected-(M1-P4.28-Pad59)") (class "Default")
      (node (ref "M1") (pin "59") (pinfunction "P4.28_59") (pintype "bidirectional"))
    )
    (net (code "142") (name "unconnected-(M1-P4.29-Pad58)") (class "Default")
      (node (ref "M1") (pin "58") (pinfunction "P4.29_58") (pintype "bidirectional"))
    )
    (net (code "143") (name "unconnected-(M1-RESET-Pad4)") (class "Default")
      (node (ref "M1") (pin "4") (pinfunction "RESET_4") (pintype "bidirectional"))
    )
    (net (code "144") (name "unconnected-(M1-VBAT-Pad3)") (class "Default")
      (node (ref "M1") (pin "3") (pinfunction "VBAT_3") (pintype "bidirectional"))
    )
    (net (code "145") (name "unconnected-(M2-PadID)") (class "Default")
      (node (ref "M2") (pin "ID") (pinfunction "ID_ID") (pintype "bidirectional"))
    )
    (net (code "146") (name "unconnected-(M3-Pad1)") (class "Default")
      (node (ref "M3") (pin "1") (pinfunction "1_1") (pintype "passive"))
    )
    (net (code "147") (name "unconnected-(M3-Pad9)") (class "Default")
      (node (ref "M3") (pin "9") (pinfunction "9_9") (pintype "passive"))
    )
    (net (code "148") (name "unconnected-(U8-R1IN-Pad4)") (class "Default")
      (node (ref "U8") (pin "4") (pinfunction "R1IN_4") (pintype "input"))
    )
    (net (code "149") (name "unconnected-(U8-R1OUT-Pad3)") (class "Default")
      (node (ref "U8") (pin "3") (pinfunction "R1OUT_3") (pintype "output"))
    )
    (net (code "150") (name "unconnected-(U8-T1IN-Pad2)") (class "Default")
      (node (ref "U8") (pin "2") (pinfunction "T1IN_2") (pintype "input"))
    )
    (net (code "151") (name "unconnected-(U8-T1OUT-Pad5)") (class "Default")
      (node (ref "U8") (pin "5") (pinfunction "T1OUT_5") (pintype "output"))
    )
  )
)
